# board.net
KiCad netlist of a schematic drawn in EAGLE
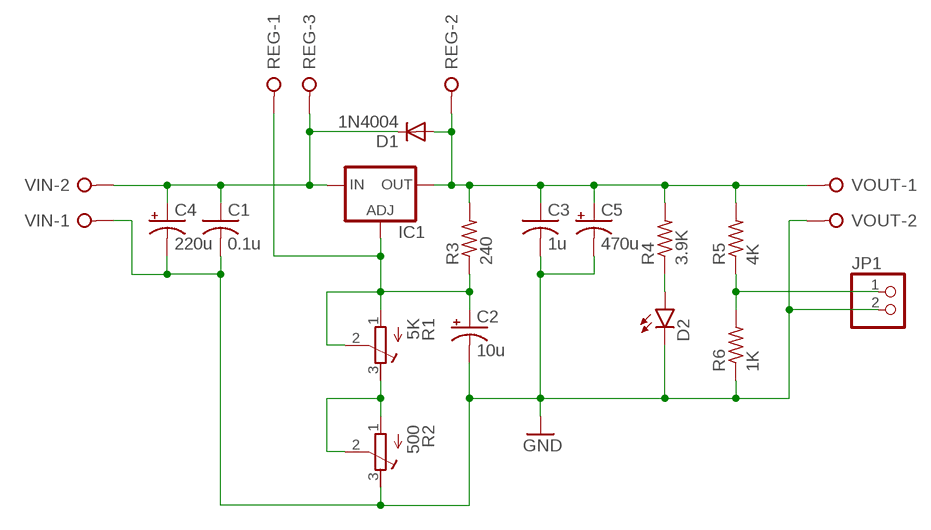
[diagram p0: schematic, sheet 1]

(export (version "E")
  (design (tool "Eeschema 10.0.6"))
  (components
    (comp (ref "C1")
      (value "0.1u")
      (footprint "eagle-import:C1206")
      (libsource (lib "eagle-import") (part "C-USC1206"))
    )
    (comp (ref "C2")
      (value "10u")
      (footprint "eagle-import:E2-5")
      (libsource (lib "eagle-import") (part "CPOL-USE2-5"))
    )
    (comp (ref "C3")
      (value "1u")
      (footprint "eagle-import:C1206")
      (libsource (lib "eagle-import") (part "C-USC1206"))
    )
    (comp (ref "C4")
      (value "220u")
      (footprint "eagle-import:E5-10,5")
      (libsource (lib "eagle-import") (part "CPOL-USE5-10.5"))
    )
    (comp (ref "C5")
      (value "470u")
      (footprint "eagle-import:E5-13")
      (libsource (lib "eagle-import") (part "CPOL-USE5-13"))
    )
    (comp (ref "D1")
      (value "1N4004")
      (footprint "eagle-import:DO41-10")
      (libsource (lib "eagle-import") (part "1N4004"))
    )
    (comp (ref "D2")
      (value "LED1206")
      (footprint "eagle-import:LED-1206")
      (libsource (lib "eagle-import") (part "LED1206"))
    )
    (comp (ref "IC1")
      (value "LM317TS")
      (footprint "eagle-import:317TS")
      (libsource (lib "eagle-import") (part "LM317TS"))
    )
    (comp (ref "JP1")
      (value "PINHD-1X2")
      (footprint "eagle-import:1X02")
      (libsource (lib "eagle-import") (part "PINHD-1X2"))
    )
    (comp (ref "R1")
      (value "5K")
      (footprint "eagle-import:RTRIM3296W")
      (libsource (lib "eagle-import") (part "R-TRIMM3296W"))
    )
    (comp (ref "R2")
      (value "500")
      (footprint "eagle-import:RTRIM3296W")
      (libsource (lib "eagle-import") (part "R-TRIMM3296W"))
    )
    (comp (ref "R3")
      (value "240")
      (footprint "eagle-import:0309_10")
      (libsource (lib "eagle-import") (part "R-US_0309/10"))
    )
    (comp (ref "R4")
      (value "3.9K")
      (footprint "eagle-import:R1206")
      (libsource (lib "eagle-import") (part "R-US_R1206"))
    )
    (comp (ref "R5")
      (value "4K")
      (footprint "eagle-import:R1206")
      (libsource (lib "eagle-import") (part "R-US_R1206"))
    )
    (comp (ref "R6")
      (value "1K")
      (footprint "eagle-import:R1206")
      (libsource (lib "eagle-import") (part "R-US_R1206"))
    )
    (comp (ref "REG")
      (value "W237-3E")
      (footprint "eagle-import:W237-3E")
      (libsource (lib "eagle-import") (part "W237-3E"))
    )
    (comp (ref "VIN")
      (value "W237-02P")
      (footprint "eagle-import:W237-132")
      (libsource (lib "eagle-import") (part "W237-02P"))
    )
    (comp (ref "VOUT")
      (value "W237-02P")
      (footprint "eagle-import:W237-132")
      (libsource (lib "eagle-import") (part "W237-02P"))
    )
  )
  (nets
    (net (code "1") (name "GND") (class "Default")
      (node (ref "C1") (pin "2") (pinfunction "2_2") (pintype "passive"))
      (node (ref "C2") (pin "-") (pinfunction "-_-") (pintype "passive"))
      (node (ref "C3") (pin "2") (pinfunction "2_2") (pintype "passive"))
      (node (ref "C4") (pin "-") (pinfunction "-_-") (pintype "passive"))
      (node (ref "C5") (pin "-") (pinfunction "-_-") (pintype "passive"))
      (node (ref "D2") (pin "C") (pinfunction "C_C") (pintype "passive"))
      (node (ref "JP1") (pin "2") (pinfunction "2_2") (pintype "passive"))
      (node (ref "R2") (pin "3") (pinfunction "E_3") (pintype "passive"))
      (node (ref "R6") (pin "1") (pinfunction "1_1") (pintype "passive"))
      (node (ref "VIN") (pin "1") (pinfunction "KL_1") (pintype "passive"))
      (node (ref "VOUT") (pin "2") (pinfunction "KL_2") (pintype "passive"))
    )
    (net (code "2") (name "Net-(D2-PadA)") (class "Default")
      (node (ref "D2") (pin "A") (pinfunction "A_A") (pintype "passive"))
      (node (ref "R4") (pin "1") (pinfunction "1_1") (pintype "passive"))
    )
    (net (code "3") (name "Net-(IC1-ADJ)") (class "Default")
      (node (ref "C2") (pin "+") (pinfunction "+_+") (pintype "passive"))
      (node (ref "IC1") (pin "1") (pinfunction "ADJ_1") (pintype "input"))
      (node (ref "R1") (pin "1") (pinfunction "A_1") (pintype "passive"))
      (node (ref "R1") (pin "2") (pinfunction "S_2") (pintype "passive"))
      (node (ref "R3") (pin "1") (pinfunction "1_1") (pintype "passive"))
      (node (ref "REG") (pin "1") (pinfunction "KL_1") (pintype "passive"))
    )
    (net (code "4") (name "Net-(IC1-IN)") (class "Default")
      (node (ref "C1") (pin "1") (pinfunction "1_1") (pintype "passive"))
      (node (ref "C4") (pin "+") (pinfunction "+_+") (pintype "passive"))
      (node (ref "D1") (pin "C") (pinfunction "C_C") (pintype "passive"))
      (node (ref "IC1") (pin "3") (pinfunction "IN_3") (pintype "input"))
      (node (ref "REG") (pin "3") (pinfunction "KL_3") (pintype "passive"))
      (node (ref "VIN") (pin "2") (pinfunction "KL_2") (pintype "passive"))
    )
    (net (code "5") (name "Net-(IC1-OUT)") (class "Default")
      (node (ref "C3") (pin "1") (pinfunction "1_1") (pintype "passive"))
      (node (ref "C5") (pin "+") (pinfunction "+_+") (pintype "passive"))
      (node (ref "D1") (pin "A") (pinfunction "A_A") (pintype "passive"))
      (node (ref "IC1") (pin "2") (pinfunction "OUT_2") (pintype "passive"))
      (node (ref "R3") (pin "2") (pinfunction "2_2") (pintype "passive"))
      (node (ref "R4") (pin "2") (pinfunction "2_2") (pintype "passive"))
      (node (ref "R5") (pin "2") (pinfunction "2_2") (pintype "passive"))
      (node (ref "REG") (pin "2") (pinfunction "KL_2") (pintype "passive"))
      (node (ref "VOUT") (pin "1") (pinfunction "KL_1") (pintype "passive"))
    )
    (net (code "6") (name "Net-(JP1-Pad1)") (class "Default")
      (node (ref "JP1") (pin "1") (pinfunction "1_1") (pintype "passive"))
      (node (ref "R5") (pin "1") (pinfunction "1_1") (pintype "passive"))
      (node (ref "R6") (pin "2") (pinfunction "2_2") (pintype "passive"))
    )
    (net (code "7") (name "Net-(R1-E)") (class "Default")
      (node (ref "R1") (pin "3") (pinfunction "E_3") (pintype "passive"))
      (node (ref "R2") (pin "1") (pinfunction "A_1") (pintype "passive"))
      (node (ref "R2") (pin "2") (pinfunction "S_2") (pintype "passive"))
    )
  )
)
